# brick_analog_light.net
KiCad netlist of a schematic drawn in EAGLE
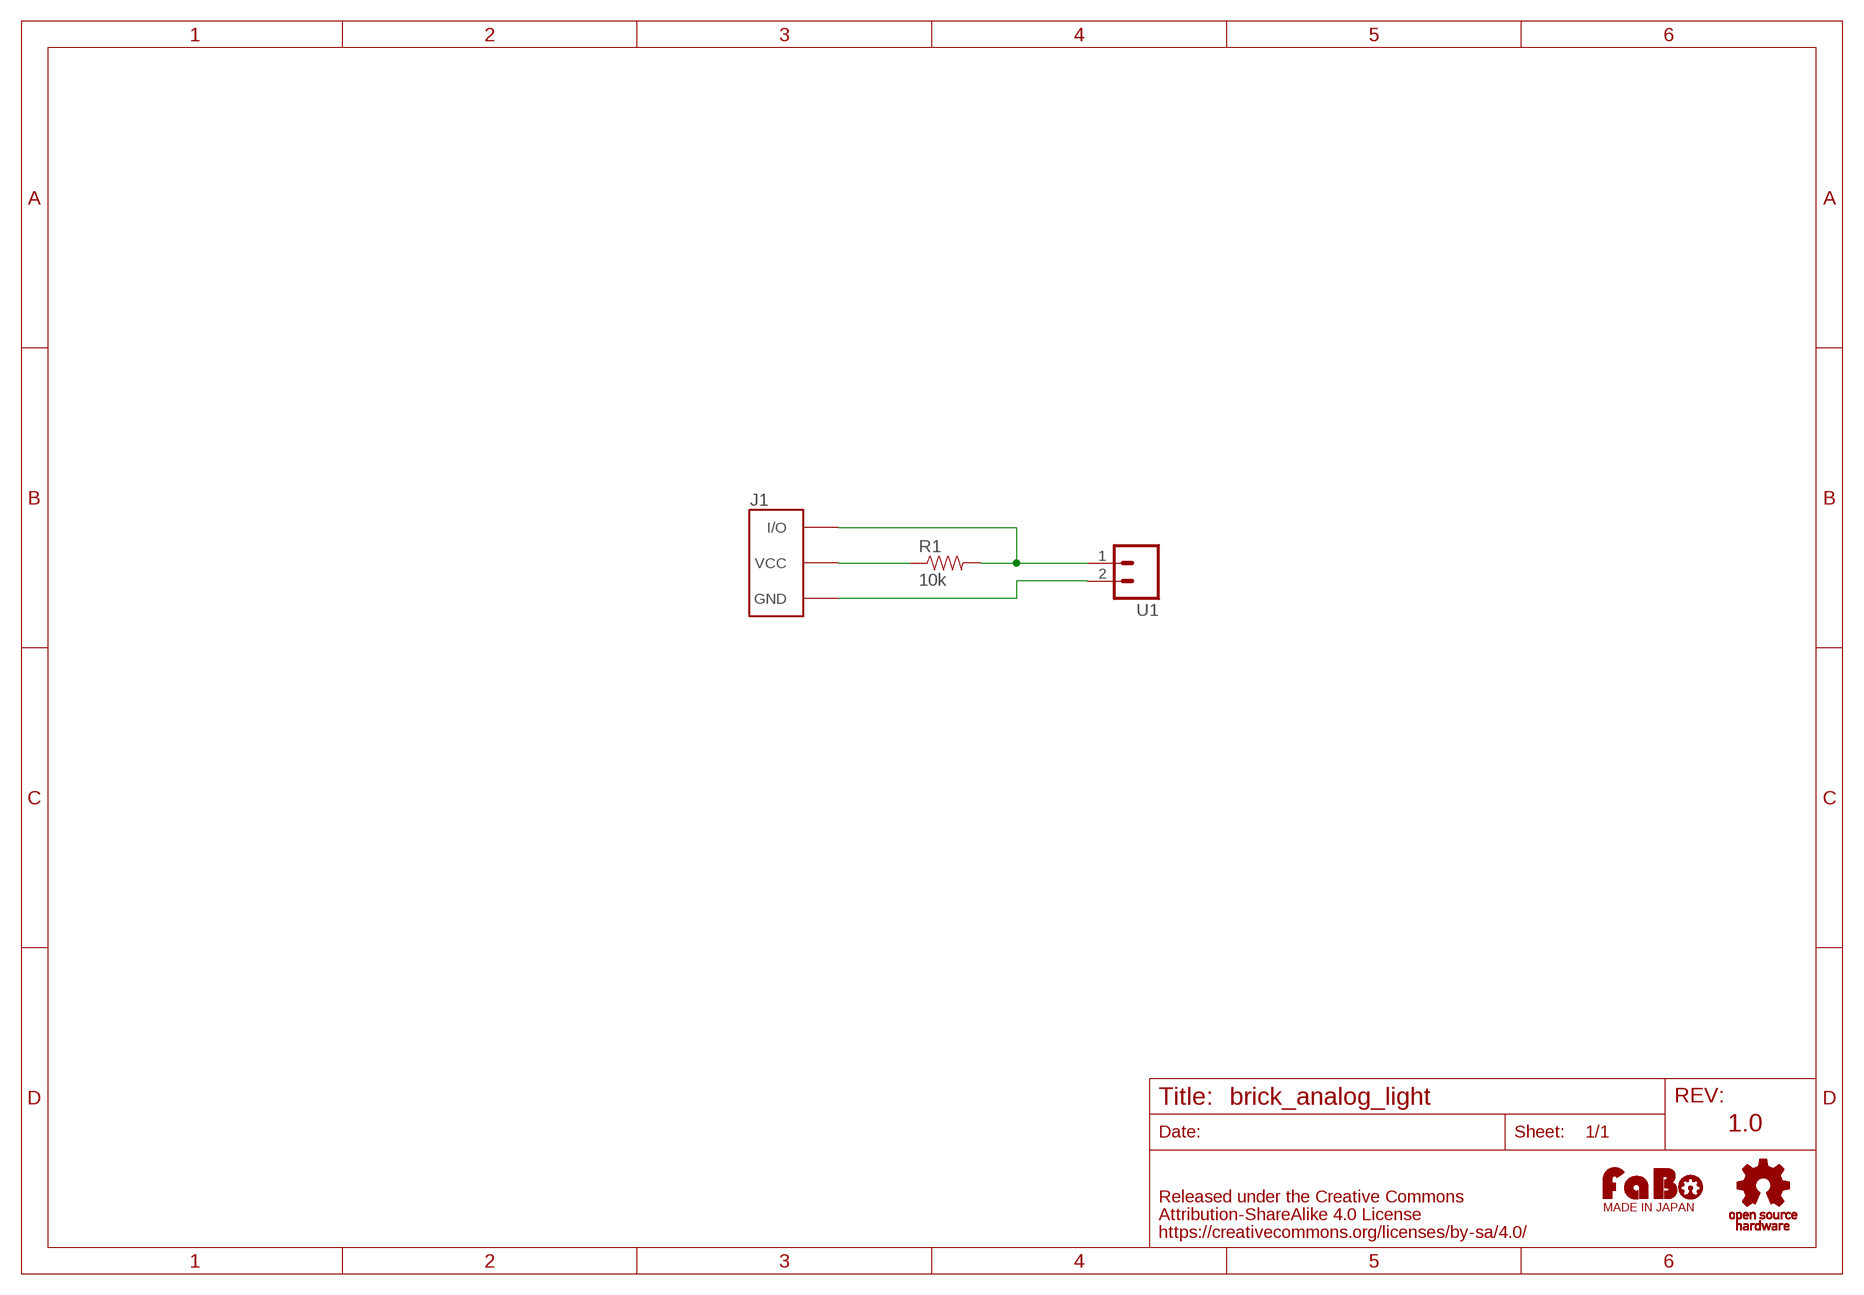
[diagram p0: schematic, sheet 1]

(export (version "E")
  (design (tool "Eeschema 10.0.6"))
  (components
    (comp (ref "J1")
      (value "BRICK_3PIN_NORMAL")
      (footprint "eagle-import:BRICK_3PIN")
      (libsource (lib "eagle-import") (part "BRICK_3PIN_NORMAL"))
    )
    (comp (ref "R1")
      (value "10k")
      (footprint "eagle-import:RES-AXL-REGULAR")
      (libsource (lib "eagle-import") (part "RES-PTH-REGULAR"))
    )
    (comp (ref "U$2")
      (value "LOGO_FABO-M")
      (footprint "eagle-import:LOGO_FABO_M")
      (libsource (lib "eagle-import") (part "LOGO_FABO-M"))
    )
    (comp (ref "U$4")
      (value "LOGO_OSHW_T-M")
      (footprint "eagle-import:LOGO_OSHW_T_M")
      (libsource (lib "eagle-import") (part "LOGO_OSHW_T-M"))
    )
    (comp (ref "U1")
      (value "M02NG")
      (footprint "eagle-import:1X02")
      (libsource (lib "eagle-import") (part "M02NG"))
    )
  )
  (nets
    (net (code "1") (name "Net-(J1-I{slash}O)") (class "Default")
      (node (ref "J1") (pin "IN/OUT") (pinfunction "I/O_IN/OUT") (pintype "bidirectional"))
      (node (ref "R1") (pin "P$2") (pinfunction "2_P$2") (pintype "passive"))
      (node (ref "U1") (pin "1") (pinfunction "1_1") (pintype "passive"))
    )
    (net (code "2") (name "Net-(J1-PadGND)") (class "Default")
      (node (ref "J1") (pin "GND") (pinfunction "GND_GND") (pintype "bidirectional"))
      (node (ref "U1") (pin "2") (pinfunction "2_2") (pintype "passive"))
    )
    (net (code "3") (name "Net-(R1-1)") (class "Default")
      (node (ref "J1") (pin "VCC") (pinfunction "VCC_VCC") (pintype "bidirectional"))
      (node (ref "R1") (pin "P$1") (pinfunction "1_P$1") (pintype "passive"))
    )
  )
)
